# 06_Audio-CODEC.net
KiCad netlist of a schematic drawn in Altium Designer
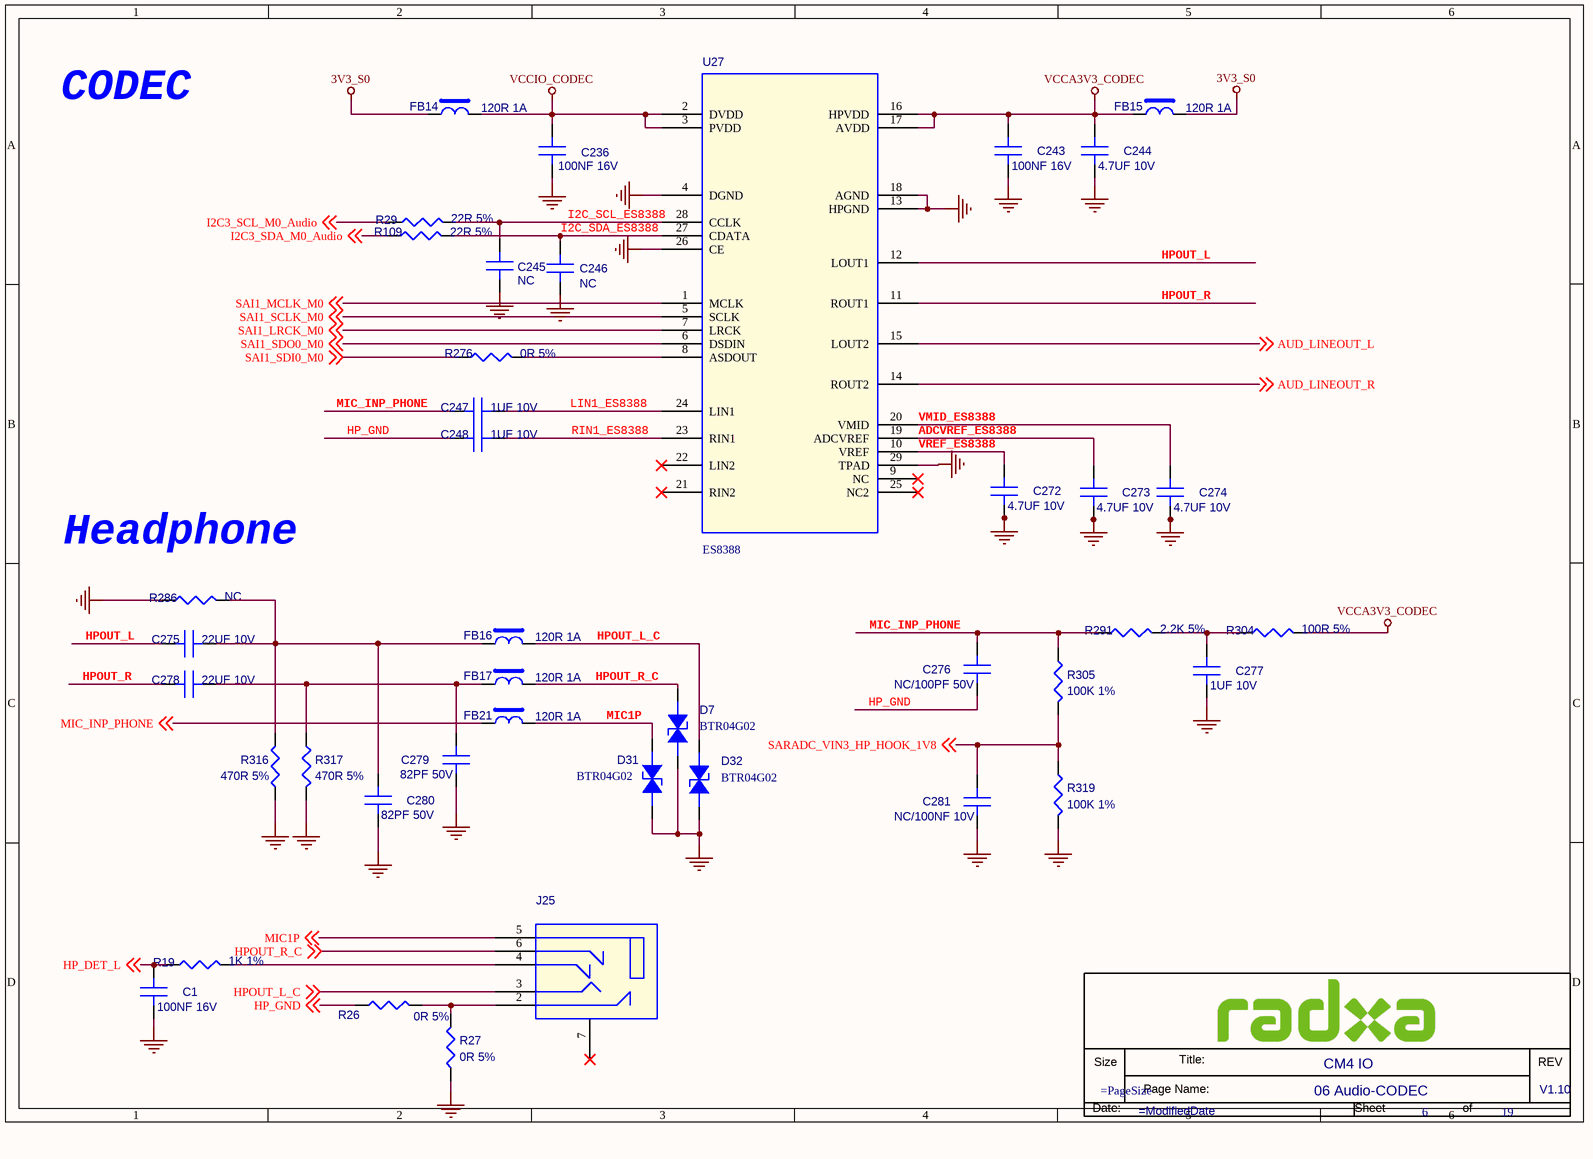
[diagram p0: 06 Audio-CODEC.SchDoc]

(export (version "E")
  (design (tool "Eeschema 10.0.6"))
  (components
    (comp (ref "C1")
      (value "100NF 16V")
      (footprint "C0201")
      (description "SMD  0201  100NF  16V  X5R  ±20%  ROHS")
      (fields (field (name "PART NUMBER") "A1C01.00099"))
      (libsource (lib "*") (part "C"))
    )
    (comp (ref "C236")
      (value "100NF 16V")
      (footprint "C0201")
      (description "SMD  0201  100NF  16V  X5R  ±20%  ROHS")
      (fields (field (name "PART NUMBER") "A1C01.00099"))
      (libsource (lib "*") (part "C"))
    )
    (comp (ref "C243")
      (value "100NF 16V")
      (footprint "C0201")
      (description "SMD  0201  100NF  16V  X5R  ±20%  ROHS")
      (fields (field (name "PART NUMBER") "A1C01.00099"))
      (libsource (lib "*") (part "C"))
    )
    (comp (ref "C244")
      (value "4.7UF 10V")
      (footprint "C0402")
      (description "SMD  0402  4.7UF  10V  X5R  ±20%  ROHS")
      (fields (field (name "PART NUMBER") "A1C01.00073"))
      (libsource (lib "*") (part "C"))
    )
    (comp (ref "C245")
      (value "NC")
      (footprint "C0201")
      (description "SMD  0201  10PF  50V  NPO  ±5%  ROHS")
      (fields (field (name "PART NUMBER") "A1C01.00141"))
      (libsource (lib "*") (part "C"))
    )
    (comp (ref "C246")
      (value "NC")
      (footprint "C0201")
      (description "SMD  0201  10PF  50V  NPO  ±5%  ROHS")
      (fields (field (name "PART NUMBER") "A1C01.00141"))
      (libsource (lib "*") (part "C"))
    )
    (comp (ref "C247")
      (value "1UF 10V")
      (footprint "C0201")
      (description "SMD  0201  1UF  10V  X5R  ±20%  ROHS")
      (fields (field (name "PART NUMBER") "A1C01.00081"))
      (libsource (lib "*") (part "C"))
    )
    (comp (ref "C248")
      (value "1UF 10V")
      (footprint "C0201")
      (description "SMD  0201  1UF  10V  X5R  ±20%  ROHS")
      (fields (field (name "PART NUMBER") "A1C01.00081"))
      (libsource (lib "*") (part "C"))
    )
    (comp (ref "C272")
      (value "4.7UF 10V")
      (footprint "C0402")
      (description "SMD  0402  4.7UF  10V  X5R  ±20%  ROHS")
      (fields (field (name "PART NUMBER") "A1C01.00073"))
      (libsource (lib "*") (part "C"))
    )
    (comp (ref "C273")
      (value "4.7UF 10V")
      (footprint "C0402")
      (description "SMD  0402  4.7UF  10V  X5R  ±20%  ROHS")
      (fields (field (name "PART NUMBER") "A1C01.00073"))
      (libsource (lib "*") (part "C"))
    )
    (comp (ref "C274")
      (value "4.7UF 10V")
      (footprint "C0402")
      (description "SMD  0402  4.7UF  10V  X5R  ±20%  ROHS")
      (fields (field (name "PART NUMBER") "A1C01.00073"))
      (libsource (lib "*") (part "C"))
    )
    (comp (ref "C275")
      (value "22UF 10V")
      (footprint "C0603")
      (description "SMD  0603  22UF  10V  X5R  ±20%  ROHS")
      (fields (field (name "PART NUMBER") "A1C01.00015"))
      (libsource (lib "*") (part "C"))
    )
    (comp (ref "C276")
      (value "NC/100PF 50V")
      (footprint "C0201")
      (description "SMD  0201  100PF  50V  NPO  ±5%  ROHS")
      (fields (field (name "PART NUMBER") "A1C01.00382"))
      (libsource (lib "*") (part "C"))
    )
    (comp (ref "C277")
      (value "1UF 10V")
      (footprint "C0201")
      (description "SMD  0201  1UF  10V  X5R  ±20%  ROHS")
      (fields (field (name "PART NUMBER") "A1C01.00081"))
      (libsource (lib "*") (part "C"))
    )
    (comp (ref "C278")
      (value "22UF 10V")
      (footprint "C0603")
      (description "SMD  0603  22UF  10V  X5R  ±20%  ROHS")
      (fields (field (name "PART NUMBER") "A1C01.00015"))
      (libsource (lib "*") (part "C"))
    )
    (comp (ref "C279")
      (value "82PF 50V")
      (footprint "C0201")
      (description "SMD  0201  82PF  50V  COG  ±2%  ROHS")
      (fields (field (name "PART NUMBER") "A1C01.00327"))
      (libsource (lib "*") (part "C"))
    )
    (comp (ref "C280")
      (value "82PF 50V")
      (footprint "C0201")
      (description "SMD  0201  82PF  50V  COG  ±2%  ROHS")
      (fields (field (name "PART NUMBER") "A1C01.00327"))
      (libsource (lib "*") (part "C"))
    )
    (comp (ref "C281")
      (value "NC/100NF 10V")
      (footprint "C0201")
      (description "SMD  0201  100NF  10V  X5R  ±20%  ROHS")
      (fields (field (name "PART NUMBER") "A1C01.00009"))
      (libsource (lib "*") (part "C"))
    )
    (comp (ref "D7")
      (value "BTR04G02")
      (footprint "DFN1006-2L")
      (description "SMD  编带  0402  BTR04G02  B-tron  ROHS")
      (fields (field (name "PART NUMBER") "A1D02.00002"))
      (libsource (lib "*") (part "ESD"))
    )
    (comp (ref "D31")
      (value "BTR04G02")
      (footprint "DFN1006-2L")
      (description "SMD  编带  0402  BTR04G02  B-tron  ROHS")
      (fields (field (name "PART NUMBER") "A1D02.00002"))
      (libsource (lib "*") (part "ESD"))
    )
    (comp (ref "D32")
      (value "BTR04G02")
      (footprint "DFN1006-2L")
      (description "SMD  编带  0402  BTR04G02  B-tron  ROHS")
      (fields (field (name "PART NUMBER") "A1D02.00002"))
      (libsource (lib "*") (part "ESD"))
    )
    (comp (ref "FB14")
      (value "120R 1A")
      (footprint "FB0201")
      (description "SMD  0201  FB120R  1A  MPZ0603S121HT000  ±25%  ROHS")
      (fields (field (name "PART NUMBER") "A1L09.00033"))
      (libsource (lib "*") (part "BEAD"))
    )
    (comp (ref "FB15")
      (value "120R 1A")
      (footprint "FB0201")
      (description "SMD  0201  FB120R  1A  MPZ0603S121HT000  ±25%  ROHS")
      (fields (field (name "PART NUMBER") "A1L09.00033"))
      (libsource (lib "") (part "BEAD_1"))
    )
    (comp (ref "FB16")
      (value "120R 1A")
      (footprint "FB0201")
      (description "SMD  0201  FB120R  1A  MPZ0603S121HT000  ±25%  ROHS")
      (fields (field (name "PART NUMBER") "A1L09.00033"))
      (libsource (lib "*") (part "BEAD"))
    )
    (comp (ref "FB17")
      (value "120R 1A")
      (footprint "FB0201")
      (description "SMD  0201  FB120R  1A  MPZ0603S121HT000  ±25%  ROHS")
      (fields (field (name "PART NUMBER") "A1L09.00033"))
      (libsource (lib "*") (part "BEAD"))
    )
    (comp (ref "FB21")
      (value "120R 1A")
      (footprint "FB0201")
      (description "SMD  0201  FB120R  1A  MPZ0603S121HT000  ±25%  ROHS")
      (fields (field (name "PART NUMBER") "A1L09.00033"))
      (libsource (lib "*") (part "BEAD"))
    )
    (comp (ref "J25")
      (value "~")
      (footprint "AUDIO_SM6_LIE")
      (description "SMD  XJ-DR-PJ342B-00  6PIN  外孔Φ6.0mm  内孔Φ3.6mm  前插后贴  14*6.4*H4.5MM  黑色  镀金铜头   协佳  ROHS")
      (fields (field (name "PART NUMBER") "A1J10.00001"))
      (libsource (lib "*") (part "PJ342B"))
    )
    (comp (ref "R19")
      (value "1K 1%")
      (footprint "R0402")
      (description "SMD  0201  1K  1/20W  ±1%  ROHS")
      (fields (field (name "PART NUMBER") "A1R01.00111"))
      (libsource (lib "*") (part "R"))
    )
    (comp (ref "R26")
      (value "0R 5%")
      (footprint "R0402")
      (description "SMD  0201  0R  1/20W  ±5%  ROHS")
      (fields (field (name "PART NUMBER") "A1R01.00027"))
      (libsource (lib "*") (part "R"))
    )
    (comp (ref "R27")
      (value "0R 5%")
      (footprint "R0402")
      (description "SMD  0201  0R  1/20W  ±5%  ROHS")
      (fields (field (name "PART NUMBER") "A1R01.00027"))
      (libsource (lib "*") (part "R"))
    )
    (comp (ref "R29")
      (value "22R 5%")
      (footprint "R0402")
      (description "SMD  0201  22R  1/20W  ±5%  ROHS")
      (fields (field (name "PART NUMBER") "A1R01.00024"))
      (libsource (lib "*") (part "R"))
    )
    (comp (ref "R109")
      (value "22R 5%")
      (footprint "R0402")
      (description "SMD  0201  22R  1/20W  ±5%  ROHS")
      (fields (field (name "PART NUMBER") "A1R01.00024"))
      (libsource (lib "*") (part "R"))
    )
    (comp (ref "R276")
      (value "0R 5%")
      (footprint "R0402")
      (description "SMD  0201  0R  1/20W  ±5%  ROHS")
      (fields (field (name "PART NUMBER") "A1R01.00027"))
      (libsource (lib "*") (part "R"))
    )
    (comp (ref "R286")
      (value "NC")
      (footprint "R0402")
      (description "SMD  0201  10K  1/20W  ±5%  ROHS")
      (fields (field (name "PART NUMBER") "A1R01.00012"))
      (libsource (lib "*") (part "R"))
    )
    (comp (ref "R291")
      (value "2.2K 5%")
      (footprint "R0402")
      (description "SMD  0201  2.2K  1/20W  ±5%  ROHS")
      (fields (field (name "PART NUMBER") "A1R01.00016"))
      (libsource (lib "*") (part "R"))
    )
    (comp (ref "R304")
      (value "100R 5%")
      (footprint "R0402")
      (description "SMD  0201  100R  1/20W  ±5%  ROHS")
      (fields (field (name "PART NUMBER") "A1R01.00023"))
      (libsource (lib "*") (part "R"))
    )
    (comp (ref "R305")
      (value "100K 1%")
      (footprint "R0402")
      (description "SMD  0201  100K  1/20W  ±1%  ROHS")
      (fields (field (name "PART NUMBER") "A1R01.00165"))
      (libsource (lib "*") (part "R"))
    )
    (comp (ref "R316")
      (value "470R 5%")
      (footprint "R0402")
      (description "SMD  0201  470R  1/20W  ±5%  ROHS")
      (fields (field (name "PART NUMBER") "A1R01.00020"))
      (libsource (lib "*") (part "R"))
    )
    (comp (ref "R317")
      (value "470R 5%")
      (footprint "R0402")
      (description "SMD  0201  470R  1/20W  ±5%  ROHS")
      (fields (field (name "PART NUMBER") "A1R01.00020"))
      (libsource (lib "*") (part "R"))
    )
    (comp (ref "R319")
      (value "100K 1%")
      (footprint "R0402")
      (description "SMD  0201  100K  1/20W  ±1%  ROHS")
      (fields (field (name "PART NUMBER") "A1R01.00165"))
      (libsource (lib "*") (part "R"))
    )
    (comp (ref "U27")
      (value "ES8388")
      (footprint "QFN28_4X4")
      (description "SMD  ADC/DAC-专用型  ES8388  QFN28  Everest-semi(顺芯)  ROHS")
      (fields (field (name "PART NUMBER") "A1I01.00762"))
      (libsource (lib "*") (part "ES8388"))
    )
  )
  (nets
    (net (code "1") (name "/ADCVREF_ES8388") (class "Default")
      (node (ref "C273") (pin "1") (pinfunction "A_1") (pintype "passive"))
      (node (ref "U27") (pin "19") (pinfunction "ADCVREF_19") (pintype "passive"))
    )
    (net (code "2") (name "/HPOUT_L") (class "Default")
      (node (ref "C275") (pin "1") (pinfunction "A_1") (pintype "passive"))
      (node (ref "U27") (pin "12") (pinfunction "LOUT1_12") (pintype "passive"))
    )
    (net (code "3") (name "/HPOUT_R") (class "Default")
      (node (ref "C278") (pin "1") (pinfunction "A_1") (pintype "passive"))
      (node (ref "U27") (pin "11") (pinfunction "ROUT1_11") (pintype "passive"))
    )
    (net (code "4") (name "/I2C_SCL_ES8388") (class "Default")
      (node (ref "C245") (pin "1") (pinfunction "A_1") (pintype "passive"))
      (node (ref "R29") (pin "2") (pinfunction "2_2") (pintype "passive"))
      (node (ref "U27") (pin "28") (pinfunction "CCLK_28") (pintype "passive"))
    )
    (net (code "5") (name "/I2C_SDA_ES8388") (class "Default")
      (node (ref "C246") (pin "1") (pinfunction "A_1") (pintype "passive"))
      (node (ref "R109") (pin "2") (pinfunction "2_2") (pintype "passive"))
      (node (ref "U27") (pin "27") (pinfunction "CDATA_27") (pintype "passive"))
    )
    (net (code "6") (name "/LIN1_ES8388") (class "Default")
      (node (ref "C247") (pin "1") (pinfunction "A_1") (pintype "passive"))
      (node (ref "U27") (pin "24") (pinfunction "LIN1_24") (pintype "passive"))
    )
    (net (code "7") (name "/RIN1_ES8388") (class "Default")
      (node (ref "C248") (pin "1") (pinfunction "A_1") (pintype "passive"))
      (node (ref "U27") (pin "23") (pinfunction "RIN1_23") (pintype "passive"))
    )
    (net (code "8") (name "/VMID_ES8388") (class "Default")
      (node (ref "C274") (pin "1") (pinfunction "A_1") (pintype "passive"))
      (node (ref "U27") (pin "20") (pinfunction "VMID_20") (pintype "passive"))
    )
    (net (code "9") (name "/VREF_ES8388") (class "Default")
      (node (ref "C272") (pin "1") (pinfunction "A_1") (pintype "passive"))
      (node (ref "U27") (pin "10") (pinfunction "VREF_10") (pintype "passive"))
    )
    (net (code "10") (name "3V3_S0") (class "Default")
      (node (ref "FB14") (pin "1") (pinfunction "1_1") (pintype "passive"))
      (node (ref "FB15") (pin "1") (pinfunction "1_1") (pintype "passive"))
    )
    (net (code "11") (name "AUD_LINEOUT_L") (class "Default")
      (node (ref "U27") (pin "15") (pinfunction "LOUT2_15") (pintype "passive"))
    )
    (net (code "12") (name "AUD_LINEOUT_R") (class "Default")
      (node (ref "U27") (pin "14") (pinfunction "ROUT2_14") (pintype "passive"))
    )
    (net (code "13") (name "GND") (class "Default")
      (node (ref "C1") (pin "2") (pinfunction "B_2") (pintype "passive"))
      (node (ref "C236") (pin "2") (pinfunction "B_2") (pintype "passive"))
      (node (ref "C243") (pin "2") (pinfunction "B_2") (pintype "passive"))
      (node (ref "C244") (pin "2") (pinfunction "B_2") (pintype "passive"))
      (node (ref "C245") (pin "2") (pinfunction "B_2") (pintype "passive"))
      (node (ref "C246") (pin "2") (pinfunction "B_2") (pintype "passive"))
      (node (ref "C272") (pin "2") (pinfunction "B_2") (pintype "passive"))
      (node (ref "C273") (pin "2") (pinfunction "B_2") (pintype "passive"))
      (node (ref "C274") (pin "2") (pinfunction "B_2") (pintype "passive"))
      (node (ref "C277") (pin "2") (pinfunction "B_2") (pintype "passive"))
      (node (ref "C279") (pin "2") (pinfunction "B_2") (pintype "passive"))
      (node (ref "C280") (pin "2") (pinfunction "B_2") (pintype "passive"))
      (node (ref "C281") (pin "2") (pinfunction "B_2") (pintype "passive"))
      (node (ref "D31") (pin "2") (pinfunction "CATHODE_2") (pintype "passive"))
      (node (ref "D32") (pin "2") (pinfunction "CATHODE_2") (pintype "passive"))
      (node (ref "D7") (pin "2") (pinfunction "CATHODE_2") (pintype "passive"))
      (node (ref "R27") (pin "1") (pinfunction "1_1") (pintype "passive"))
      (node (ref "R286") (pin "1") (pinfunction "1_1") (pintype "passive"))
      (node (ref "R316") (pin "2") (pinfunction "2_2") (pintype "passive"))
      (node (ref "R317") (pin "2") (pinfunction "2_2") (pintype "passive"))
      (node (ref "R319") (pin "2") (pinfunction "2_2") (pintype "passive"))
      (node (ref "U27") (pin "13") (pinfunction "HPGND_13") (pintype "passive"))
      (node (ref "U27") (pin "18") (pinfunction "AGND_18") (pintype "passive"))
      (node (ref "U27") (pin "26") (pinfunction "CE_26") (pintype "passive"))
      (node (ref "U27") (pin "29") (pinfunction "TPAD_29") (pintype "passive"))
      (node (ref "U27") (pin "4") (pinfunction "DGND_4") (pintype "passive"))
    )
    (net (code "14") (name "HPOUT_L_C") (class "Default")
      (node (ref "D32") (pin "1") (pinfunction "ANODE_1") (pintype "passive"))
      (node (ref "FB16") (pin "2") (pinfunction "2_2") (pintype "passive"))
      (node (ref "J25") (pin "3") (pinfunction "R_3") (pintype "passive"))
    )
    (net (code "15") (name "HPOUT_R_C") (class "Default")
      (node (ref "D7") (pin "1") (pinfunction "ANODE_1") (pintype "passive"))
      (node (ref "FB17") (pin "2") (pinfunction "2_2") (pintype "passive"))
      (node (ref "J25") (pin "6") (pinfunction "HP_6") (pintype "passive"))
    )
    (net (code "16") (name "HP_DET_L") (class "Default")
      (node (ref "C1") (pin "1") (pinfunction "A_1") (pintype "passive"))
      (node (ref "R19") (pin "1") (pinfunction "1_1") (pintype "passive"))
    )
    (net (code "17") (name "HP_GND") (class "Default")
      (node (ref "C248") (pin "2") (pinfunction "B_2") (pintype "passive"))
      (node (ref "C276") (pin "2") (pinfunction "B_2") (pintype "passive"))
      (node (ref "R26") (pin "1") (pinfunction "1_1") (pintype "passive"))
    )
    (net (code "18") (name "I2C3_SCL_M0_Audio") (class "Default")
      (node (ref "R29") (pin "1") (pinfunction "1_1") (pintype "passive"))
    )
    (net (code "19") (name "I2C3_SDA_M0_Audio") (class "Default")
      (node (ref "R109") (pin "1") (pinfunction "1_1") (pintype "passive"))
    )
    (net (code "20") (name "MIC1P") (class "Default")
      (node (ref "D31") (pin "1") (pinfunction "ANODE_1") (pintype "passive"))
      (node (ref "FB21") (pin "2") (pinfunction "2_2") (pintype "passive"))
      (node (ref "J25") (pin "5") (pinfunction "D_5") (pintype "passive"))
    )
    (net (code "21") (name "MIC_INP_PHONE") (class "Default")
      (node (ref "C247") (pin "2") (pinfunction "B_2") (pintype "passive"))
      (node (ref "C276") (pin "1") (pinfunction "A_1") (pintype "passive"))
      (node (ref "FB21") (pin "1") (pinfunction "1_1") (pintype "passive"))
      (node (ref "R291") (pin "1") (pinfunction "1_1") (pintype "passive"))
      (node (ref "R305") (pin "1") (pinfunction "1_1") (pintype "passive"))
    )
    (net (code "22") (name "Net-(C275-B)") (class "Default")
      (node (ref "C275") (pin "2") (pinfunction "B_2") (pintype "passive"))
      (node (ref "C280") (pin "1") (pinfunction "A_1") (pintype "passive"))
      (node (ref "FB16") (pin "1") (pinfunction "1_1") (pintype "passive"))
      (node (ref "R286") (pin "2") (pinfunction "2_2") (pintype "passive"))
      (node (ref "R316") (pin "1") (pinfunction "1_1") (pintype "passive"))
    )
    (net (code "23") (name "Net-(C277-A)") (class "Default")
      (node (ref "C277") (pin "1") (pinfunction "A_1") (pintype "passive"))
      (node (ref "R291") (pin "2") (pinfunction "2_2") (pintype "passive"))
      (node (ref "R304") (pin "1") (pinfunction "1_1") (pintype "passive"))
    )
    (net (code "24") (name "Net-(C278-B)") (class "Default")
      (node (ref "C278") (pin "2") (pinfunction "B_2") (pintype "passive"))
      (node (ref "C279") (pin "1") (pinfunction "A_1") (pintype "passive"))
      (node (ref "FB17") (pin "1") (pinfunction "1_1") (pintype "passive"))
      (node (ref "R317") (pin "1") (pinfunction "1_1") (pintype "passive"))
    )
    (net (code "25") (name "Net-(J25-DH)") (class "Default")
      (node (ref "J25") (pin "2") (pinfunction "DH_2") (pintype "passive"))
      (node (ref "R26") (pin "2") (pinfunction "2_2") (pintype "passive"))
      (node (ref "R27") (pin "2") (pinfunction "2_2") (pintype "passive"))
    )
    (net (code "26") (name "Net-(J25-L)") (class "Default")
      (node (ref "J25") (pin "4") (pinfunction "L_4") (pintype "passive"))
      (node (ref "R19") (pin "2") (pinfunction "2_2") (pintype "passive"))
    )
    (net (code "27") (name "Net-(U27-ASDOUT)") (class "Default")
      (node (ref "R276") (pin "2") (pinfunction "2_2") (pintype "passive"))
      (node (ref "U27") (pin "8") (pinfunction "ASDOUT_8") (pintype "passive"))
    )
    (net (code "28") (name "SAI1_LRCK_M0") (class "Default")
      (node (ref "U27") (pin "7") (pinfunction "LRCK_7") (pintype "passive"))
    )
    (net (code "29") (name "SAI1_MCLK_M0") (class "Default")
      (node (ref "U27") (pin "1") (pinfunction "MCLK_1") (pintype "passive"))
    )
    (net (code "30") (name "SAI1_SCLK_M0") (class "Default")
      (node (ref "U27") (pin "5") (pinfunction "SCLK_5") (pintype "passive"))
    )
    (net (code "31") (name "SAI1_SDI0_M0") (class "Default")
      (node (ref "R276") (pin "1") (pinfunction "1_1") (pintype "passive"))
    )
    (net (code "32") (name "SAI1_SDO0_M0") (class "Default")
      (node (ref "U27") (pin "6") (pinfunction "DSDIN_6") (pintype "passive"))
    )
    (net (code "33") (name "SARADC_VIN3_HP_HOOK_1V8") (class "Default")
      (node (ref "C281") (pin "1") (pinfunction "A_1") (pintype "passive"))
      (node (ref "R305") (pin "2") (pinfunction "2_2") (pintype "passive"))
      (node (ref "R319") (pin "1") (pinfunction "1_1") (pintype "passive"))
    )
    (net (code "34") (name "VCCA3V3_CODEC") (class "Default")
      (node (ref "C243") (pin "1") (pinfunction "A_1") (pintype "passive"))
      (node (ref "C244") (pin "1") (pinfunction "A_1") (pintype "passive"))
      (node (ref "FB15") (pin "2") (pinfunction "2_2") (pintype "passive"))
      (node (ref "R304") (pin "2") (pinfunction "2_2") (pintype "passive"))
      (node (ref "U27") (pin "16") (pinfunction "HPVDD_16") (pintype "passive"))
      (node (ref "U27") (pin "17") (pinfunction "AVDD_17") (pintype "passive"))
    )
    (net (code "35") (name "VCCIO_CODEC") (class "Default")
      (node (ref "C236") (pin "1") (pinfunction "A_1") (pintype "passive"))
      (node (ref "FB14") (pin "2") (pinfunction "2_2") (pintype "passive"))
      (node (ref "U27") (pin "2") (pinfunction "DVDD_2") (pintype "passive"))
      (node (ref "U27") (pin "3") (pinfunction "PVDD_3") (pintype "passive"))
    )
    (net (code "36") (name "unconnected-(J25-NC2-Pad7)") (class "Default")
      (node (ref "J25") (pin "7") (pinfunction "NC2_7") (pintype "passive+no_connect"))
    )
    (net (code "37") (name "unconnected-(U27-LIN2-Pad22)") (class "Default")
      (node (ref "U27") (pin "22") (pinfunction "LIN2_22") (pintype "passive+no_connect"))
    )
    (net (code "38") (name "unconnected-(U27-NC-Pad9)") (class "Default")
      (node (ref "U27") (pin "9") (pinfunction "NC_9") (pintype "passive+no_connect"))
    )
    (net (code "39") (name "unconnected-(U27-NC2-Pad25)") (class "Default")
      (node (ref "U27") (pin "25") (pinfunction "NC2_25") (pintype "passive+no_connect"))
    )
    (net (code "40") (name "unconnected-(U27-RIN2-Pad21)") (class "Default")
      (node (ref "U27") (pin "21") (pinfunction "RIN2_21") (pintype "passive+no_connect"))
    )
  )
)
